# Main_Board_IO.net
KiCad netlist of a schematic drawn in Altium Designer
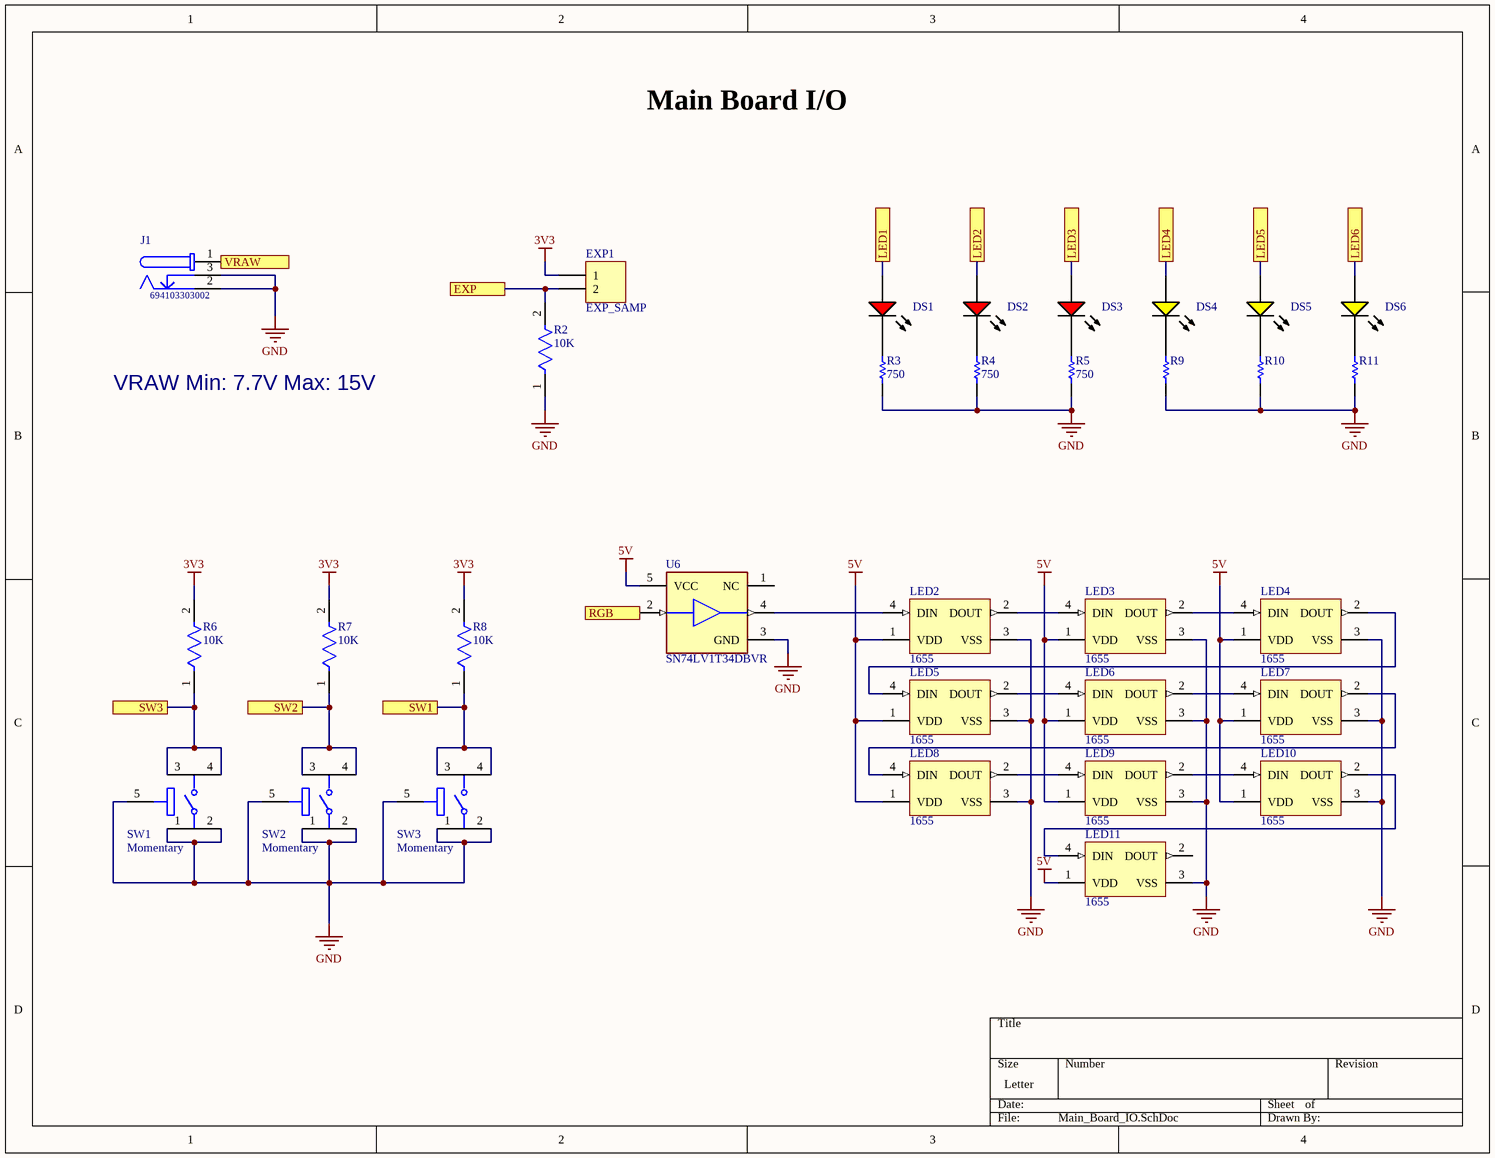
[diagram p0: Main_Board_IO.SchDoc]

(export (version "E")
  (design (tool "Eeschema 10.0.6"))
  (components
    (comp (ref "DS1")
      (value "TLMS1000-GS08")
      (footprint "VISH-TLMS1000_V")
      (description "Low Current LED, 40 mW, 1.8 V, -40 to 100 degC, 2-Pin SMD (0603), RoHS, Tape and Reel")
      (fields (field (name "MANUFACTURER") "Vishay"))
      (libsource (lib "Altium Content Vault") (part "LED-RED-AK-2"))
    )
    (comp (ref "DS2")
      (value "TLMS1000-GS08")
      (footprint "VISH-TLMS1000_V")
      (description "Low Current LED, 40 mW, 1.8 V, -40 to 100 degC, 2-Pin SMD (0603), RoHS, Tape and Reel")
      (fields (field (name "MANUFACTURER") "Vishay"))
      (libsource (lib "Altium Content Vault") (part "LED-RED-AK-2"))
    )
    (comp (ref "DS3")
      (value "TLMS1000-GS08")
      (footprint "VISH-TLMS1000_V")
      (description "Low Current LED, 40 mW, 1.8 V, -40 to 100 degC, 2-Pin SMD (0603), RoHS, Tape and Reel")
      (fields (field (name "MANUFACTURER") "Vishay"))
      (libsource (lib "Altium Content Vault") (part "LED-RED-AK-2"))
    )
    (comp (ref "DS4")
      (value "TLMY1000-GS08")
      (footprint "VISH-TLMY1000_V")
      (description "Low Current LED, 40 mW, -40 to 100 degC, 2-Pin SMD, RoHS, Tape and Reel")
      (fields (field (name "MANUFACTURER") "Vishay"))
      (libsource (lib "Altium Content Vault") (part "LED-YELLOW-AK-2"))
    )
    (comp (ref "DS5")
      (value "TLMY1000-GS08")
      (footprint "VISH-TLMY1000_V")
      (description "Low Current LED, 40 mW, -40 to 100 degC, 2-Pin SMD, RoHS, Tape and Reel")
      (fields (field (name "MANUFACTURER") "Vishay"))
      (libsource (lib "Altium Content Vault") (part "LED-YELLOW-AK-2"))
    )
    (comp (ref "DS6")
      (value "TLMY1000-GS08")
      (footprint "VISH-TLMY1000_V")
      (description "Low Current LED, 40 mW, -40 to 100 degC, 2-Pin SMD, RoHS, Tape and Reel")
      (fields (field (name "MANUFACTURER") "Vishay"))
      (libsource (lib "Altium Content Vault") (part "LED-YELLOW-AK-2"))
    )
    (comp (ref "EXP1")
      (value "EXP_SAMP")
      (footprint "HDR1X2")
      (description "Header, 2-Pin")
      (fields (field (name "PUBLISHER") "Altium Limited"))
      (libsource (lib "Miscellaneous Connectors") (part "Header 2"))
    )
    (comp (ref "J1")
      (value "694103303002")
      (footprint "694103303002")
      (description "DC Power Jack Connector WR-DC, Male, Right Angled, THT, 2 A, 30 V")
      (fields (field (name "MANUFACTURER") "Wurth Elektronik") (field (name "PUBLISHER") "WurthElektronik"))
      (libsource (lib "Altium Content Vault") (part "WE-JACK-2CD3-RN"))
    )
    (comp (ref "LED2")
      (value "1655")
      (footprint "ADA-RGB-1655_V")
      (fields (field (name "MANUFACTURER") "Adafruit-Industries-LLC"))
      (libsource (lib "Altium Content Vault") (part "ADA-RGB-1655-4"))
    )
    (comp (ref "LED3")
      (value "1655")
      (footprint "ADA-RGB-1655_V")
      (fields (field (name "MANUFACTURER") "Adafruit-Industries-LLC"))
      (libsource (lib "Altium Content Vault") (part "ADA-RGB-1655-4"))
    )
    (comp (ref "LED4")
      (value "1655")
      (footprint "ADA-RGB-1655_V")
      (fields (field (name "MANUFACTURER") "Adafruit-Industries-LLC"))
      (libsource (lib "Altium Content Vault") (part "ADA-RGB-1655-4"))
    )
    (comp (ref "LED5")
      (value "1655")
      (footprint "ADA-RGB-1655_V")
      (fields (field (name "MANUFACTURER") "Adafruit-Industries-LLC"))
      (libsource (lib "Altium Content Vault") (part "ADA-RGB-1655-4"))
    )
    (comp (ref "LED6")
      (value "1655")
      (footprint "ADA-RGB-1655_V")
      (fields (field (name "MANUFACTURER") "Adafruit-Industries-LLC"))
      (libsource (lib "Altium Content Vault") (part "ADA-RGB-1655-4"))
    )
    (comp (ref "LED7")
      (value "1655")
      (footprint "ADA-RGB-1655_V")
      (fields (field (name "MANUFACTURER") "Adafruit-Industries-LLC"))
      (libsource (lib "Altium Content Vault") (part "ADA-RGB-1655-4"))
    )
    (comp (ref "LED8")
      (value "1655")
      (footprint "ADA-RGB-1655_V")
      (fields (field (name "MANUFACTURER") "Adafruit-Industries-LLC"))
      (libsource (lib "Altium Content Vault") (part "ADA-RGB-1655-4"))
    )
    (comp (ref "LED9")
      (value "1655")
      (footprint "ADA-RGB-1655_V")
      (fields (field (name "MANUFACTURER") "Adafruit-Industries-LLC"))
      (libsource (lib "Altium Content Vault") (part "ADA-RGB-1655-4"))
    )
    (comp (ref "LED10")
      (value "1655")
      (footprint "ADA-RGB-1655_V")
      (fields (field (name "MANUFACTURER") "Adafruit-Industries-LLC"))
      (libsource (lib "Altium Content Vault") (part "ADA-RGB-1655-4"))
    )
    (comp (ref "LED11")
      (value "1655")
      (footprint "ADA-RGB-1655_V")
      (fields (field (name "MANUFACTURER") "Adafruit-Industries-LLC"))
      (libsource (lib "Altium Content Vault") (part "ADA-RGB-1655-4"))
    )
    (comp (ref "R2")
      (value "10K")
      (footprint "FP-CR1206-IPC_B")
      (description "Thick Film Chip Resistors 1206 10kΩ 0.25W 5% 200ppm/°C")
      (fields (field (name "TOLERANCE") "5%"))
      (libsource (lib "Altium Content Vault") (part "1029c3af85768c4190bb7ad29bc67b5"))
    )
    (comp (ref "R3")
      (value "750")
      (footprint "RESC2013X50X40LL20T20")
      (fields (field (name "MANUFACTURER") "Susumu") (field (name "PART NUMBER") "RR1220P-331-D"))
      (libsource (lib "Altium Content Vault") (part "RES"))
    )
    (comp (ref "R4")
      (value "750")
      (footprint "RESC2013X50X40LL20T20")
      (fields (field (name "MANUFACTURER") "Susumu") (field (name "PART NUMBER") "RR1220P-331-D"))
      (libsource (lib "Altium Content Vault") (part "RES"))
    )
    (comp (ref "R5")
      (value "750")
      (footprint "RESC2013X50X40LL20T20")
      (fields (field (name "MANUFACTURER") "Susumu") (field (name "PART NUMBER") "RR1220P-331-D"))
      (libsource (lib "Altium Content Vault") (part "RES"))
    )
    (comp (ref "R6")
      (value "10K")
      (footprint "FP-CR1206-IPC_B")
      (description "Thick Film Chip Resistors 1206 10kΩ 0.25W 5% 200ppm/°C")
      (fields (field (name "TOLERANCE") "5%"))
      (libsource (lib "Altium Content Vault") (part "1029c3af85768c4190bb7ad29bc67b5"))
    )
    (comp (ref "R7")
      (value "10K")
      (footprint "FP-CR1206-IPC_B")
      (description "Thick Film Chip Resistors 1206 10kΩ 0.25W 5% 200ppm/°C")
      (fields (field (name "TOLERANCE") "5%"))
      (libsource (lib "Altium Content Vault") (part "1029c3af85768c4190bb7ad29bc67b5"))
    )
    (comp (ref "R8")
      (value "10K")
      (footprint "FP-CR1206-IPC_B")
      (description "Thick Film Chip Resistors 1206 10kΩ 0.25W 5% 200ppm/°C")
      (fields (field (name "TOLERANCE") "5%"))
      (libsource (lib "Altium Content Vault") (part "1029c3af85768c4190bb7ad29bc67b5"))
    )
    (comp (ref "R9")
      (value "RR1220P-331-D")
      (footprint "RESC2013X50X40LL20T20")
      (fields (field (name "MANUFACTURER") "Susumu"))
      (libsource (lib "Altium Content Vault") (part "RES"))
    )
    (comp (ref "R10")
      (value "RR1220P-331-D")
      (footprint "RESC2013X50X40LL20T20")
      (fields (field (name "MANUFACTURER") "Susumu"))
      (libsource (lib "Altium Content Vault") (part "RES"))
    )
    (comp (ref "R11")
      (value "RR1220P-331-D")
      (footprint "RESC2013X50X40LL20T20")
      (fields (field (name "MANUFACTURER") "Susumu"))
      (libsource (lib "Altium Content Vault") (part "RES"))
    )
    (comp (ref "SW1")
      (value "Momentary")
      (footprint "FP-B3SN-3112P-MFG")
      (description "SWITCH TACTILE SPST-NO 0.05A 24V")
      (libsource (lib "Altium Content Vault") (part "97d78ac1cd4af81980cd836935afc5b"))
    )
    (comp (ref "SW2")
      (value "Momentary")
      (footprint "FP-B3SN-3112P-MFG")
      (description "SWITCH TACTILE SPST-NO 0.05A 24V")
      (libsource (lib "Altium Content Vault") (part "97d78ac1cd4af81980cd836935afc5b"))
    )
    (comp (ref "SW3")
      (value "Momentary")
      (footprint "FP-B3SN-3112P-MFG")
      (description "SWITCH TACTILE SPST-NO 0.05A 24V")
      (libsource (lib "Altium Content Vault") (part "97d78ac1cd4af81980cd836935afc5b"))
    )
    (comp (ref "U6")
      (value "SN74LV1T34DBVR")
      (footprint "FP-DBV0005A-IPC_B")
      (description "IC BUF NON-INVERT 5.5V SOT23-5")
      (libsource (lib "Altium Content Vault") (part "d03805866fcc65e5014dff611fc4129"))
    )
  )
  (nets
    (net (code "1") (name "/EXP") (class "Default")
      (node (ref "EXP1") (pin "2") (pinfunction "2_2") (pintype "passive"))
      (node (ref "R2") (pin "2") (pinfunction "2_2") (pintype "passive"))
    )
    (net (code "2") (name "/LED1") (class "Default")
      (node (ref "DS1") (pin "1") (pinfunction "A_1") (pintype "passive"))
    )
    (net (code "3") (name "/LED2") (class "Default")
      (node (ref "DS2") (pin "1") (pinfunction "A_1") (pintype "passive"))
    )
    (net (code "4") (name "/LED3") (class "Default")
      (node (ref "DS3") (pin "1") (pinfunction "A_1") (pintype "passive"))
    )
    (net (code "5") (name "/LED4") (class "Default")
      (node (ref "DS4") (pin "1") (pinfunction "A_1") (pintype "passive"))
    )
    (net (code "6") (name "/LED5") (class "Default")
      (node (ref "DS5") (pin "1") (pinfunction "A_1") (pintype "passive"))
    )
    (net (code "7") (name "/LED6") (class "Default")
      (node (ref "DS6") (pin "1") (pinfunction "A_1") (pintype "passive"))
    )
    (net (code "8") (name "/RGB") (class "Default")
      (node (ref "U6") (pin "2") (pinfunction "A_2") (pintype "input"))
    )
    (net (code "9") (name "/SW1") (class "Default")
      (node (ref "R8") (pin "1") (pinfunction "1_1") (pintype "passive"))
      (node (ref "SW3") (pin "3") (pinfunction "3_3") (pintype "passive"))
      (node (ref "SW3") (pin "4") (pinfunction "4_4") (pintype "passive"))
    )
    (net (code "10") (name "/SW2") (class "Default")
      (node (ref "R7") (pin "1") (pinfunction "1_1") (pintype "passive"))
      (node (ref "SW2") (pin "3") (pinfunction "3_3") (pintype "passive"))
      (node (ref "SW2") (pin "4") (pinfunction "4_4") (pintype "passive"))
    )
    (net (code "11") (name "/SW3") (class "Default")
      (node (ref "R6") (pin "1") (pinfunction "1_1") (pintype "passive"))
      (node (ref "SW1") (pin "3") (pinfunction "3_3") (pintype "passive"))
      (node (ref "SW1") (pin "4") (pinfunction "4_4") (pintype "passive"))
    )
    (net (code "12") (name "/VRAW") (class "Default")
      (node (ref "J1") (pin "1") (pinfunction "1_1") (pintype "passive"))
    )
    (net (code "13") (name "3V3") (class "Default")
      (node (ref "EXP1") (pin "1") (pinfunction "1_1") (pintype "passive"))
      (node (ref "R6") (pin "2") (pinfunction "2_2") (pintype "passive"))
      (node (ref "R7") (pin "2") (pinfunction "2_2") (pintype "passive"))
      (node (ref "R8") (pin "2") (pinfunction "2_2") (pintype "passive"))
    )
    (net (code "14") (name "5V") (class "Default")
      (node (ref "LED10") (pin "1") (pinfunction "VDD_1") (pintype "power_in"))
      (node (ref "LED11") (pin "1") (pinfunction "VDD_1") (pintype "power_in"))
      (node (ref "LED2") (pin "1") (pinfunction "VDD_1") (pintype "power_in"))
      (node (ref "LED3") (pin "1") (pinfunction "VDD_1") (pintype "power_in"))
      (node (ref "LED4") (pin "1") (pinfunction "VDD_1") (pintype "power_in"))
      (node (ref "LED5") (pin "1") (pinfunction "VDD_1") (pintype "power_in"))
      (node (ref "LED6") (pin "1") (pinfunction "VDD_1") (pintype "power_in"))
      (node (ref "LED7") (pin "1") (pinfunction "VDD_1") (pintype "power_in"))
      (node (ref "LED8") (pin "1") (pinfunction "VDD_1") (pintype "power_in"))
      (node (ref "LED9") (pin "1") (pinfunction "VDD_1") (pintype "power_in"))
      (node (ref "U6") (pin "5") (pinfunction "VCC_5") (pintype "power_in"))
    )
    (net (code "15") (name "GND") (class "Default")
      (node (ref "J1") (pin "2") (pinfunction "2_2") (pintype "passive"))
      (node (ref "J1") (pin "3") (pinfunction "3_3") (pintype "passive"))
      (node (ref "LED10") (pin "3") (pinfunction "VSS_3") (pintype "power_in"))
      (node (ref "LED11") (pin "3") (pinfunction "VSS_3") (pintype "power_in"))
      (node (ref "LED2") (pin "3") (pinfunction "VSS_3") (pintype "power_in"))
      (node (ref "LED3") (pin "3") (pinfunction "VSS_3") (pintype "power_in"))
      (node (ref "LED4") (pin "3") (pinfunction "VSS_3") (pintype "power_in"))
      (node (ref "LED5") (pin "3") (pinfunction "VSS_3") (pintype "power_in"))
      (node (ref "LED6") (pin "3") (pinfunction "VSS_3") (pintype "power_in"))
      (node (ref "LED7") (pin "3") (pinfunction "VSS_3") (pintype "power_in"))
      (node (ref "LED8") (pin "3") (pinfunction "VSS_3") (pintype "power_in"))
      (node (ref "LED9") (pin "3") (pinfunction "VSS_3") (pintype "power_in"))
      (node (ref "R10") (pin "1") (pinfunction "1_1") (pintype "passive"))
      (node (ref "R11") (pin "1") (pinfunction "1_1") (pintype "passive"))
      (node (ref "R2") (pin "1") (pinfunction "1_1") (pintype "passive"))
      (node (ref "R3") (pin "1") (pinfunction "1_1") (pintype "passive"))
      (node (ref "R4") (pin "1") (pinfunction "1_1") (pintype "passive"))
      (node (ref "R5") (pin "1") (pinfunction "1_1") (pintype "passive"))
      (node (ref "R9") (pin "1") (pinfunction "1_1") (pintype "passive"))
      (node (ref "SW1") (pin "1") (pinfunction "1_1") (pintype "passive"))
      (node (ref "SW1") (pin "2") (pinfunction "2_2") (pintype "passive"))
      (node (ref "SW1") (pin "5") (pinfunction "5_5") (pintype "passive"))
      (node (ref "SW2") (pin "1") (pinfunction "1_1") (pintype "passive"))
      (node (ref "SW2") (pin "2") (pinfunction "2_2") (pintype "passive"))
      (node (ref "SW2") (pin "5") (pinfunction "5_5") (pintype "passive"))
      (node (ref "SW3") (pin "1") (pinfunction "1_1") (pintype "passive"))
      (node (ref "SW3") (pin "2") (pinfunction "2_2") (pintype "passive"))
      (node (ref "SW3") (pin "5") (pinfunction "5_5") (pintype "passive"))
      (node (ref "U6") (pin "3") (pinfunction "GND_3") (pintype "power_in"))
    )
    (net (code "16") (name "Net-(DS1-K)") (class "Default")
      (node (ref "DS1") (pin "2") (pinfunction "K_2") (pintype "passive"))
      (node (ref "R3") (pin "2") (pinfunction "2_2") (pintype "passive"))
    )
    (net (code "17") (name "Net-(DS2-K)") (class "Default")
      (node (ref "DS2") (pin "2") (pinfunction "K_2") (pintype "passive"))
      (node (ref "R4") (pin "2") (pinfunction "2_2") (pintype "passive"))
    )
    (net (code "18") (name "Net-(DS3-K)") (class "Default")
      (node (ref "DS3") (pin "2") (pinfunction "K_2") (pintype "passive"))
      (node (ref "R5") (pin "2") (pinfunction "2_2") (pintype "passive"))
    )
    (net (code "19") (name "Net-(DS4-K)") (class "Default")
      (node (ref "DS4") (pin "2") (pinfunction "K_2") (pintype "passive"))
      (node (ref "R9") (pin "2") (pinfunction "2_2") (pintype "passive"))
    )
    (net (code "20") (name "Net-(DS5-K)") (class "Default")
      (node (ref "DS5") (pin "2") (pinfunction "K_2") (pintype "passive"))
      (node (ref "R10") (pin "2") (pinfunction "2_2") (pintype "passive"))
    )
    (net (code "21") (name "Net-(DS6-K)") (class "Default")
      (node (ref "DS6") (pin "2") (pinfunction "K_2") (pintype "passive"))
      (node (ref "R11") (pin "2") (pinfunction "2_2") (pintype "passive"))
    )
    (net (code "22") (name "Net-(LED2-DIN)") (class "Default")
      (node (ref "LED2") (pin "4") (pinfunction "DIN_4") (pintype "input"))
      (node (ref "U6") (pin "4") (pinfunction "Y_4") (pintype "output"))
    )
    (net (code "23") (name "Net-(LED2-DOUT)") (class "Default")
      (node (ref "LED2") (pin "2") (pinfunction "DOUT_2") (pintype "output"))
      (node (ref "LED3") (pin "4") (pinfunction "DIN_4") (pintype "input"))
    )
    (net (code "24") (name "Net-(LED3-DOUT)") (class "Default")
      (node (ref "LED3") (pin "2") (pinfunction "DOUT_2") (pintype "output"))
      (node (ref "LED4") (pin "4") (pinfunction "DIN_4") (pintype "input"))
    )
    (net (code "25") (name "Net-(LED4-DOUT)") (class "Default")
      (node (ref "LED4") (pin "2") (pinfunction "DOUT_2") (pintype "output"))
      (node (ref "LED5") (pin "4") (pinfunction "DIN_4") (pintype "input"))
    )
    (net (code "26") (name "Net-(LED5-DOUT)") (class "Default")
      (node (ref "LED5") (pin "2") (pinfunction "DOUT_2") (pintype "output"))
      (node (ref "LED6") (pin "4") (pinfunction "DIN_4") (pintype "input"))
    )
    (net (code "27") (name "Net-(LED6-DOUT)") (class "Default")
      (node (ref "LED6") (pin "2") (pinfunction "DOUT_2") (pintype "output"))
      (node (ref "LED7") (pin "4") (pinfunction "DIN_4") (pintype "input"))
    )
    (net (code "28") (name "Net-(LED7-DOUT)") (class "Default")
      (node (ref "LED7") (pin "2") (pinfunction "DOUT_2") (pintype "output"))
      (node (ref "LED8") (pin "4") (pinfunction "DIN_4") (pintype "input"))
    )
    (net (code "29") (name "Net-(LED8-DOUT)") (class "Default")
      (node (ref "LED8") (pin "2") (pinfunction "DOUT_2") (pintype "output"))
      (node (ref "LED9") (pin "4") (pinfunction "DIN_4") (pintype "input"))
    )
    (net (code "30") (name "Net-(LED10-DIN)") (class "Default")
      (node (ref "LED10") (pin "4") (pinfunction "DIN_4") (pintype "input"))
      (node (ref "LED9") (pin "2") (pinfunction "DOUT_2") (pintype "output"))
    )
    (net (code "31") (name "Net-(LED10-DOUT)") (class "Default")
      (node (ref "LED10") (pin "2") (pinfunction "DOUT_2") (pintype "output"))
      (node (ref "LED11") (pin "4") (pinfunction "DIN_4") (pintype "input"))
    )
    (net (code "32") (name "unconnected-(LED11-DOUT-Pad2)") (class "Default")
      (node (ref "LED11") (pin "2") (pinfunction "DOUT_2") (pintype "output"))
    )
    (net (code "33") (name "unconnected-(U6-NC-Pad1)") (class "Default")
      (node (ref "U6") (pin "1") (pinfunction "NC_1") (pintype "passive"))
    )
  )
)
